# RF.net
KiCad netlist of a schematic drawn in Altium Designer
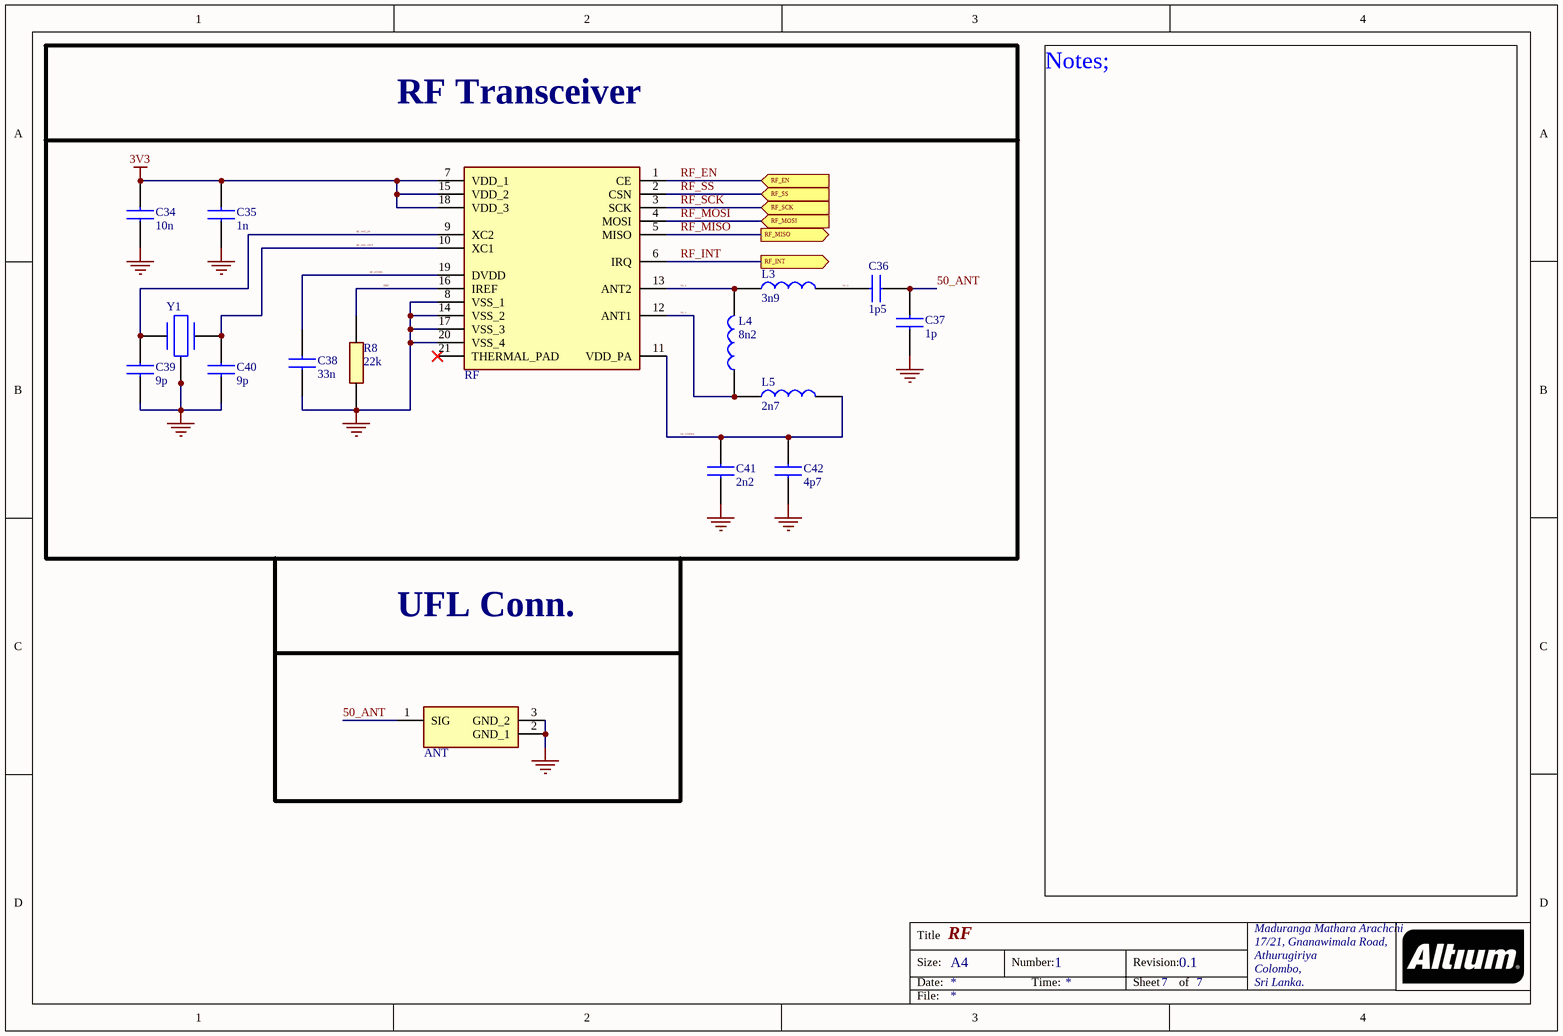
[diagram p0: RF.SchDoc]

(export (version "E")
  (design (tool "Eeschema 10.0.6"))
  (components
    (comp (ref "ANT")
      (value "CONUFL001-SMD-T")
      (footprint "RC_Car:CONUFL001SMDT")
      (description "Connector")
      (libsource (lib "RC_Car") (part "CONUFL001-SMD-T"))
    )
    (comp (ref "C34")
      (value "10n")
      (footprint "RC_Car:C0402C104J4RACTU")
      (description "Capacitor")
      (fields (field (name "MANUFACTURER_PART_NUMBER") "C0402C103K3RECTU"))
      (libsource (lib "RC_Car") (part "C0402C103K3RECTU"))
    )
    (comp (ref "C35")
      (value "1n")
      (footprint "RC_Car:C0402C104J4RACTU")
      (description "Capacitor")
      (fields
        (field (name "MANUFACTURER_PART_NUMBER") "C0402C102K3RAC")
        (field (name "MOUSER PART NUMBER") "80-C0402C102K3RAC")
      )
      (libsource (lib "RC_Car") (part "C0402C102K3RAC"))
    )
    (comp (ref "C36")
      (value "1p5")
      (footprint "RC_Car:CAPC1005X70N")
      (description "Capacitor")
      (fields (field (name "MANUFACTURER_PART_NUMBER") "GRM1555C1E1R5BA01D"))
      (libsource (lib "RC_Car") (part "GRM1555C1E1R5BA01D"))
    )
    (comp (ref "C37")
      (value "1p")
      (footprint "RC_Car:CAPC1005X70N")
      (description "Capacitor")
      (fields
        (field (name "MANUFACTURER_PART_NUMBER") "GRM1555C1E1R0BA01D")
        (field (name "MOUSER PART NUMBER") "81-GRM1555C1E1R0BA1D")
      )
      (libsource (lib "RC_Car") (part "GRM1555C1E1R0BA01D"))
    )
    (comp (ref "C38")
      (value "33n")
      (footprint "RC_Car:CAPC1005X70N")
      (description "Capacitor")
      (fields
        (field (name "MANUFACTURER_PART_NUMBER") "GRM155R71E333KA88D")
        (field (name "MOUSER PART NUMBER") "81-GRM155R71E333KA8D")
      )
      (libsource (lib "RC_Car") (part "GRM155R71E333KA88D"))
    )
    (comp (ref "C39")
      (value "9p")
      (footprint "RC_Car:CAPC1005X70N")
      (description "Capacitor")
      (fields (field (name "MANUFACTURER_PART_NUMBER") "GRM1555C1E9R0WA01J"))
      (libsource (lib "RC_Car") (part "GRM1555C1E9R0WA01J"))
    )
    (comp (ref "C40")
      (value "9p")
      (footprint "RC_Car:CAPC1005X70N")
      (description "Capacitor")
      (fields (field (name "MANUFACTURER_PART_NUMBER") "GRM1555C1E9R0WA01J"))
      (libsource (lib "RC_Car") (part "GRM1555C1E9R0WA01J"))
    )
    (comp (ref "C41")
      (value "2n2")
      (footprint "RC_Car:CAPC1005X56N")
      (description "Capacitor")
      (fields
        (field (name "MANUFACTURER_PART_NUMBER") "04023C222KAT2A")
        (field (name "MOUSER PART NUMBER") "581-04023C222KAT2A")
      )
      (libsource (lib "RC_Car") (part "04023C222KAT2A"))
    )
    (comp (ref "C42")
      (value "4p7")
      (footprint "RC_Car:CAPC1005X70N")
      (description "Capacitor")
      (fields
        (field (name "MANUFACTURER_PART_NUMBER") "GRM1555C1E4R7BA01D")
        (field (name "MOUSER PART NUMBER") "81-GRM1555C1E4R7BA1D")
      )
      (libsource (lib "RC_Car") (part "GRM1555C1E4R7BA01D"))
    )
    (comp (ref "L3")
      (value "3n9")
      (footprint "RC_Car:LQW15AN10NG80D")
      (description "Inductor")
      (fields
        (field (name "MANUFACTURER_PART_NUMBER") "LQW15AN3N9G80D")
        (field (name "MOUSER PART NUMBER") "81-LQW15AN3N9G80D")
      )
      (libsource (lib "RC_Car") (part "LQW15AN3N9G80D"))
    )
    (comp (ref "L4")
      (value "8n2")
      (footprint "RC_Car:LQG15WH0N7B02D")
      (description "Inductor")
      (fields
        (field (name "MANUFACTURER_PART_NUMBER") "LQG15HS8N2G02D")
        (field (name "MOUSER PART NUMBER") "81-LQG15HS8N2G02D")
      )
      (libsource (lib "RC_Car") (part "LQG15HS8N2G02D"))
    )
    (comp (ref "L5")
      (value "2n7")
      (footprint "RC_Car:LQW15CNR20J00B")
      (description "Inductor")
      (fields
        (field (name "MANUFACTURER_PART_NUMBER") "LQW15AN2N7G8ZD")
        (field (name "MOUSER PART NUMBER") "81-LQW15AN2N7G8ZD")
      )
      (libsource (lib "RC_Car") (part "LQW15AN2N7G8ZD"))
    )
    (comp (ref "R8")
      (value "22k")
      (footprint "RC_Car:ERJ2RKD1004X")
      (description "Resistor")
      (fields
        (field (name "MANUFACTURER_PART_NUMBER") "ERJ-2RKF2202X")
        (field (name "MOUSER PART NUMBER") "667-ERJ-2RKF2202X")
      )
      (libsource (lib "RC_Car") (part "ERJ-2RKF2202X"))
    )
    (comp (ref "RF")
      (value "NRF24L01P-R7")
      (footprint "RC_Car:QFN50P400X400X95-21N-D")
      (description "Integrated Circuit")
      (fields (field (name "MOUSER PART NUMBER") "949-NRF24L01P-R7"))
      (libsource (lib "RC_Car") (part "NRF24L01P-R7"))
    )
    (comp (ref "Y1")
      (value "TSX-3225_16.0000MF18X-AC0")
      (footprint "RC_Car:TSX3225160000MF18XAC0")
      (description "16MHz Crystal")
      (fields
        (field (name "MANUFACTURER_PART_NUMBER") "TSX-3225 16.0000MF18X-AC0")
        (field (name "MOUSER PART NUMBER") "732-322516F18XAC0")
      )
      (libsource (lib "RC_Car") (part "TSX-3225_16.0000MF18X-AC0"))
    )
  )
  (nets
    (net (code "1") (name "/50_1") (class "Default")
      (node (ref "L4") (pin "1") (pinfunction "1_1") (pintype "passive"))
      (node (ref "L5") (pin "1") (pinfunction "1_1") (pintype "passive"))
      (node (ref "RF") (pin "12") (pinfunction "ANT1_12") (pintype "passive"))
    )
    (net (code "2") (name "/50_2") (class "Default")
      (node (ref "L3") (pin "1") (pinfunction "1_1") (pintype "passive"))
      (node (ref "L4") (pin "2") (pinfunction "2_2") (pintype "passive"))
      (node (ref "RF") (pin "13") (pinfunction "ANT2_13") (pintype "passive"))
    )
    (net (code "3") (name "/50_3") (class "Default")
      (node (ref "C36") (pin "1") (pinfunction "1_1") (pintype "passive"))
      (node (ref "L3") (pin "2") (pinfunction "2_2") (pintype "passive"))
    )
    (net (code "4") (name "/50_ANT") (class "Default")
      (node (ref "ANT") (pin "1") (pinfunction "SIG_1") (pintype "passive"))
      (node (ref "C36") (pin "2") (pinfunction "2_2") (pintype "passive"))
      (node (ref "C37") (pin "2") (pinfunction "2_2") (pintype "passive"))
    )
    (net (code "5") (name "/50_VDDPA") (class "Default")
      (node (ref "C41") (pin "2") (pinfunction "2_2") (pintype "passive"))
      (node (ref "C42") (pin "2") (pinfunction "2_2") (pintype "passive"))
      (node (ref "L5") (pin "2") (pinfunction "2_2") (pintype "passive"))
      (node (ref "RF") (pin "11") (pinfunction "VDD_PA_11") (pintype "passive"))
    )
    (net (code "6") (name "/IREF") (class "Default")
      (node (ref "R8") (pin "2") (pinfunction "2_2") (pintype "passive"))
      (node (ref "RF") (pin "16") (pinfunction "IREF_16") (pintype "passive"))
    )
    (net (code "7") (name "/RF_DVDD") (class "Default")
      (node (ref "C38") (pin "2") (pinfunction "2_2") (pintype "passive"))
      (node (ref "RF") (pin "19") (pinfunction "DVDD_19") (pintype "passive"))
    )
    (net (code "8") (name "/RF_EN") (class "Default")
      (node (ref "RF") (pin "1") (pinfunction "CE_1") (pintype "passive"))
    )
    (net (code "9") (name "/RF_INT") (class "Default")
      (node (ref "RF") (pin "6") (pinfunction "IRQ_6") (pintype "passive"))
    )
    (net (code "10") (name "/RF_MISO") (class "Default")
      (node (ref "RF") (pin "5") (pinfunction "MISO_5") (pintype "passive"))
    )
    (net (code "11") (name "/RF_MOSI") (class "Default")
      (node (ref "RF") (pin "4") (pinfunction "MOSI_4") (pintype "passive"))
    )
    (net (code "12") (name "/RF_OSC_IN") (class "Default")
      (node (ref "C39") (pin "2") (pinfunction "2_2") (pintype "passive"))
      (node (ref "RF") (pin "9") (pinfunction "XC2_9") (pintype "passive"))
      (node (ref "Y1") (pin "1") (pinfunction "CRYSTAL_1_1") (pintype "passive"))
    )
    (net (code "13") (name "/RF_OSC_OUT") (class "Default")
      (node (ref "C40") (pin "2") (pinfunction "2_2") (pintype "passive"))
      (node (ref "RF") (pin "10") (pinfunction "XC1_10") (pintype "passive"))
      (node (ref "Y1") (pin "3") (pinfunction "CRYSTAL_2_3") (pintype "passive"))
    )
    (net (code "14") (name "/RF_SCK") (class "Default")
      (node (ref "RF") (pin "3") (pinfunction "SCK_3") (pintype "passive"))
    )
    (net (code "15") (name "/RF_SS") (class "Default")
      (node (ref "RF") (pin "2") (pinfunction "CSN_2") (pintype "passive"))
    )
    (net (code "16") (name "3V3") (class "Default")
      (node (ref "C34") (pin "2") (pinfunction "2_2") (pintype "passive"))
      (node (ref "C35") (pin "2") (pinfunction "2_2") (pintype "passive"))
      (node (ref "RF") (pin "15") (pinfunction "VDD_2_15") (pintype "passive"))
      (node (ref "RF") (pin "18") (pinfunction "VDD_3_18") (pintype "passive"))
      (node (ref "RF") (pin "7") (pinfunction "VDD_1_7") (pintype "passive"))
    )
    (net (code "17") (name "GND") (class "Default")
      (node (ref "ANT") (pin "2") (pinfunction "GND_1_2") (pintype "passive"))
      (node (ref "ANT") (pin "3") (pinfunction "GND_2_3") (pintype "passive"))
      (node (ref "C34") (pin "1") (pinfunction "1_1") (pintype "passive"))
      (node (ref "C35") (pin "1") (pinfunction "1_1") (pintype "passive"))
      (node (ref "C37") (pin "1") (pinfunction "1_1") (pintype "passive"))
      (node (ref "C38") (pin "1") (pinfunction "1_1") (pintype "passive"))
      (node (ref "C39") (pin "1") (pinfunction "1_1") (pintype "passive"))
      (node (ref "C40") (pin "1") (pinfunction "1_1") (pintype "passive"))
      (node (ref "C41") (pin "1") (pinfunction "1_1") (pintype "passive"))
      (node (ref "C42") (pin "1") (pinfunction "1_1") (pintype "passive"))
      (node (ref "R8") (pin "1") (pinfunction "1_1") (pintype "passive"))
      (node (ref "RF") (pin "14") (pinfunction "VSS_2_14") (pintype "passive"))
      (node (ref "RF") (pin "17") (pinfunction "VSS_3_17") (pintype "passive"))
      (node (ref "RF") (pin "20") (pinfunction "VSS_4_20") (pintype "passive"))
      (node (ref "RF") (pin "8") (pinfunction "VSS_1_8") (pintype "passive"))
      (node (ref "Y1") (pin "2") (pinfunction "GND_1_2") (pintype "passive"))
      (node (ref "Y1") (pin "4") (pinfunction "GND_2_4") (pintype "passive"))
    )
    (net (code "18") (name "unconnected-(RFA-THERMAL_PAD-Pad21)") (class "Default")
      (node (ref "RF") (pin "21") (pinfunction "THERMAL_PAD_21") (pintype "passive+no_connect"))
    )
  )
)
